# RFID_transmitter_V2.net
KiCad netlist of a schematic drawn in Altium Designer
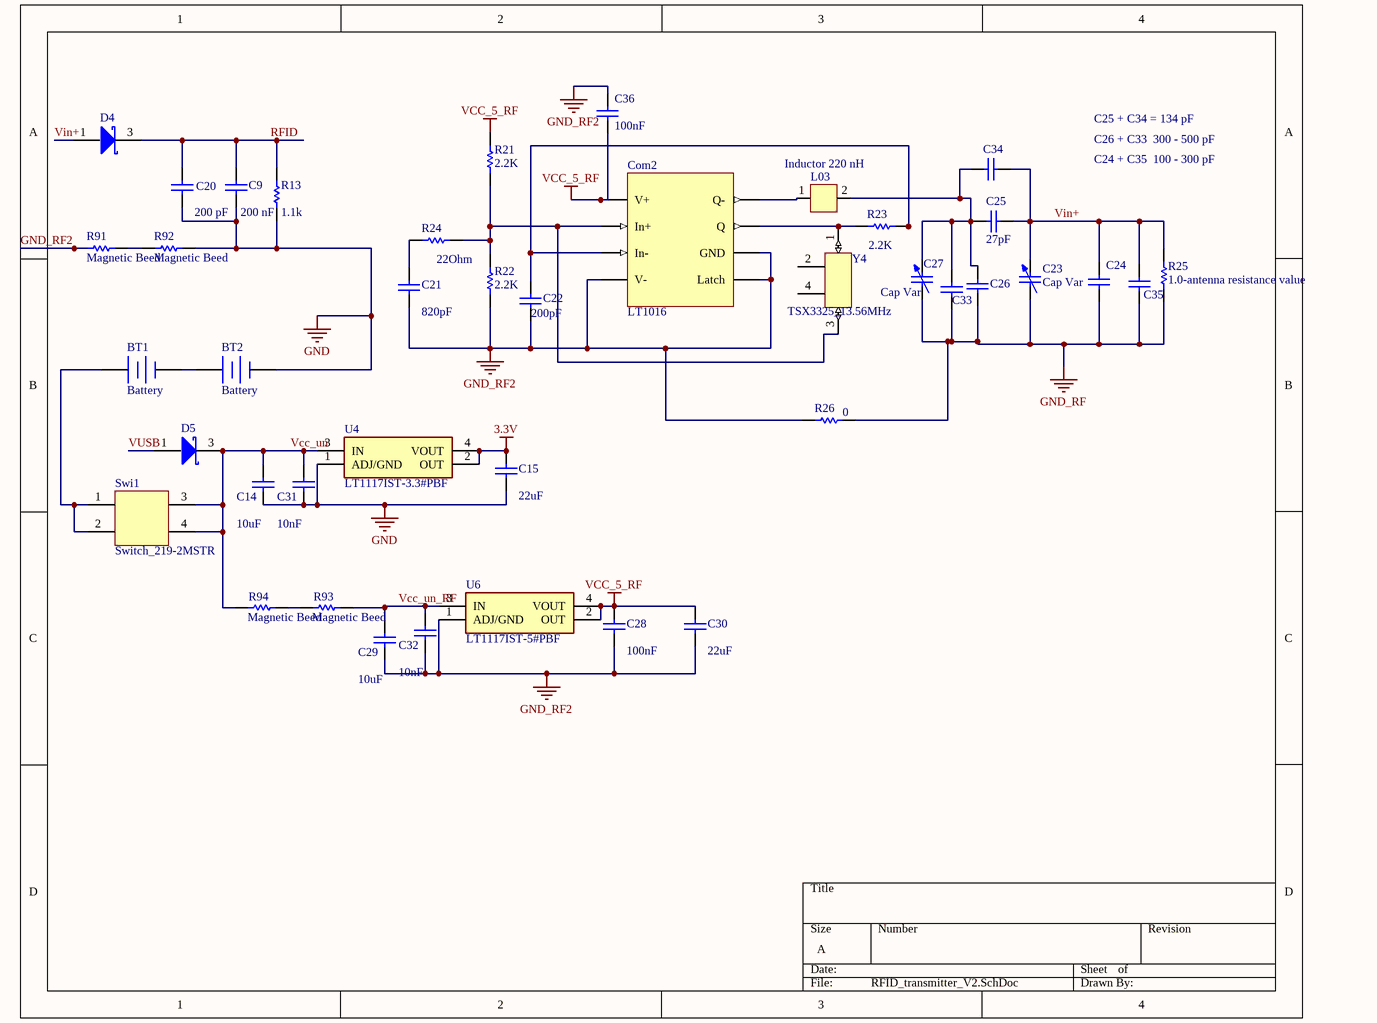
[diagram p0: RFID_transmitter_V2.SchDoc]

(export (version "E")
  (design (tool "Eeschema 10.0.6"))
  (components
    (comp (ref "BT1")
      (value "Battery")
      (footprint "Battery")
      (description "Multicell Battery")
      (fields (field (name "PUBLISHER") "Altium Limited"))
      (libsource (lib "Miscellaneous Devices") (part "Battery"))
    )
    (comp (ref "BT2")
      (value "Battery")
      (footprint "Battery")
      (description "Multicell Battery")
      (fields (field (name "PUBLISHER") "Altium Limited"))
      (libsource (lib "Miscellaneous Devices") (part "Battery"))
    )
    (comp (ref "C9")
      (value "200 nF")
      (footprint "0603")
      (description "Capacitor")
      (fields (field (name "Comment") "Cap 10n") (field (name "PUBLISHER") "Altium Limited"))
      (libsource (lib "Miscellaneous Devices") (part "Cap"))
    )
    (comp (ref "C14")
      (value "10uF")
      (footprint "0603")
      (description "Capacitor")
      (fields (field (name "Comment") "Cap 10u") (field (name "PUBLISHER") "Altium Limited"))
      (libsource (lib "Miscellaneous Devices") (part "Cap"))
    )
    (comp (ref "C15")
      (value "22uF")
      (footprint "0603")
      (description "Capacitor")
      (fields (field (name "Comment") "Cap 22u") (field (name "PUBLISHER") "Altium Limited"))
      (libsource (lib "Miscellaneous Devices") (part "Cap"))
    )
    (comp (ref "C20")
      (value "200 pF")
      (footprint "0603")
      (description "Capacitor")
      (fields (field (name "Comment") "Cap 4.7n") (field (name "PUBLISHER") "Altium Limited"))
      (libsource (lib "Miscellaneous Devices") (part "Cap"))
    )
    (comp (ref "C21")
      (value "820pF")
      (footprint "0603")
      (description "Capacitor")
      (fields (field (name "Comment") "Cap 820p") (field (name "PUBLISHER") "Altium Limited"))
      (libsource (lib "Miscellaneous Devices") (part "Cap"))
    )
    (comp (ref "C22")
      (value "200pF")
      (footprint "0603")
      (description "Capacitor")
      (fields (field (name "Comment") "Cap 200p") (field (name "PUBLISHER") "Altium Limited"))
      (libsource (lib "Miscellaneous Devices") (part "Cap"))
    )
    (comp (ref "C23")
      (value "Cap Var")
      (footprint "Variable_Capacitor_JZ400HV1")
      (description "Variable or Adjustable Capacitor")
      (fields (field (name "PUBLISHER") "Altium Limited"))
      (libsource (lib "Miscellaneous Devices") (part "Cap Var"))
    )
    (comp (ref "C24")
      (value "Cap")
      (footprint "0603")
      (description "Capacitor_for resonance")
      (fields (field (name "PUBLISHER") "Altium Limited"))
      (libsource (lib "Miscellaneous Devices") (part "Cap"))
    )
    (comp (ref "C25")
      (value "27pF")
      (footprint "0603")
      (description "Capacitor_for resonance")
      (fields (field (name "Comment") "Cap") (field (name "PUBLISHER") "Altium Limited"))
      (libsource (lib "Miscellaneous Devices") (part "Cap"))
    )
    (comp (ref "C26")
      (value "random value needs carefully address")
      (footprint "0603")
      (description "Capacitor_for resonance")
      (fields (field (name "PUBLISHER") "Altium Limited"))
      (libsource (lib "Miscellaneous Devices") (part "Cap"))
    )
    (comp (ref "C27")
      (value "Cap Var")
      (footprint "Variable_Capacitor_JZ400HV1")
      (description "Variable or Adjustable Capacitor")
      (fields (field (name "PUBLISHER") "Altium Limited"))
      (libsource (lib "Miscellaneous Devices") (part "Cap Var"))
    )
    (comp (ref "C28")
      (value "100nF")
      (footprint "0603")
      (description "Capacitor")
      (fields (field (name "Comment") "Cap 100n") (field (name "PUBLISHER") "Altium Limited"))
      (libsource (lib "Miscellaneous Devices") (part "Cap"))
    )
    (comp (ref "C29")
      (value "10uF")
      (footprint "0603")
      (description "Capacitor")
      (fields (field (name "Comment") "Cap 10u") (field (name "PUBLISHER") "Altium Limited"))
      (libsource (lib "Miscellaneous Devices") (part "Cap"))
    )
    (comp (ref "C30")
      (value "22uF")
      (footprint "0603")
      (description "Capacitor")
      (fields (field (name "Comment") "Cap 22u") (field (name "PUBLISHER") "Altium Limited"))
      (libsource (lib "Miscellaneous Devices") (part "Cap"))
    )
    (comp (ref "C31")
      (value "10nF")
      (footprint "0603")
      (description "Capacitor")
      (fields (field (name "Comment") "Cap 10n") (field (name "PUBLISHER") "Altium Limited"))
      (libsource (lib "Miscellaneous Devices") (part "Cap"))
    )
    (comp (ref "C32")
      (value "10nF")
      (footprint "0603")
      (description "Capacitor")
      (fields (field (name "Comment") "Cap 10n") (field (name "PUBLISHER") "Altium Limited"))
      (libsource (lib "Miscellaneous Devices") (part "Cap"))
    )
    (comp (ref "C33")
      (value "random value needs carefully address")
      (footprint "0603")
      (description "Capacitor_for resonance")
      (fields (field (name "PUBLISHER") "Altium Limited"))
      (libsource (lib "Miscellaneous Devices") (part "Cap"))
    )
    (comp (ref "C34")
      (value "Cap")
      (footprint "0603")
      (description "Capacitor_for resonance")
      (fields (field (name "PUBLISHER") "Altium Limited"))
      (libsource (lib "Miscellaneous Devices") (part "Cap"))
    )
    (comp (ref "C35")
      (value "Cap")
      (footprint "0603")
      (description "Capacitor_for resonance")
      (fields (field (name "PUBLISHER") "Altium Limited"))
      (libsource (lib "Miscellaneous Devices") (part "Cap"))
    )
    (comp (ref "C36")
      (value "100nF")
      (footprint "1608[0603]")
      (description "Capacitor (Semiconductor SIM Model)")
      (fields
        (field (name "VOLTAGE") "10V")
        (field (name "Comment") "GRM188R61A226ME15D")
        (field (name "PUBLISHER") "Altium Limited")
      )
      (libsource (lib "Miscellaneous Devices") (part "Cap Semi"))
    )
    (comp (ref "Com2") (value "LT1016") (footprint "LT1016_SOIC") (libsource (lib "LT1016") (part "LT1016")))
    (comp (ref "D4")
      (value "SMMBD301LT3G")
      (footprint "SamacSys:SOT96P237X111-3N")
      (description "Schottky Barrier Diodes")
      (libsource (lib "SamacSys") (part "SMMBD301LT3G"))
    )
    (comp (ref "D5")
      (value "SMMBD301LT3G")
      (footprint "SamacSys:SOT96P237X111-3N")
      (description "Schottky Barrier Diodes")
      (libsource (lib "SamacSys") (part "SMMBD301LT3G"))
    )
    (comp (ref "L03")
      (value "Inductor 220 nH")
      (footprint "Ferrite_bead_0805inch_2012mm")
      (description "220nH")
      (libsource (lib "ferrite_bead") (part "Component_1"))
    )
    (comp (ref "R13")
      (value "1.1k")
      (footprint "0603")
      (description "Resistor")
      (fields (field (name "Comment") "Res1") (field (name "PUBLISHER") "Altium Limited"))
      (libsource (lib "Miscellaneous Devices") (part "Res1"))
    )
    (comp (ref "R21")
      (value "2.2K")
      (footprint "0603")
      (description "Resistor")
      (fields (field (name "Comment") "Res1 2.2k") (field (name "PUBLISHER") "Altium Limited"))
      (libsource (lib "Miscellaneous Devices") (part "Res1"))
    )
    (comp (ref "R22")
      (value "2.2K")
      (footprint "0603")
      (description "Resistor")
      (fields (field (name "Comment") "Res1 2.2k") (field (name "PUBLISHER") "Altium Limited"))
      (libsource (lib "Miscellaneous Devices") (part "Res1"))
    )
    (comp (ref "R23")
      (value "2.2K")
      (footprint "0603")
      (description "Resistor")
      (fields (field (name "Comment") "Res1 2.2k") (field (name "PUBLISHER") "Altium Limited"))
      (libsource (lib "Miscellaneous Devices") (part "Res1"))
    )
    (comp (ref "R24")
      (value "22Ohm")
      (footprint "0603")
      (description "Resistor")
      (fields (field (name "Comment") "Res1 22") (field (name "PUBLISHER") "Altium Limited"))
      (libsource (lib "Miscellaneous Devices") (part "Res1"))
    )
    (comp (ref "R25")
      (value "1.0-antenna resistance value")
      (footprint "0603")
      (description "Resistor")
      (fields (field (name "PUBLISHER") "Altium Limited"))
      (libsource (lib "Miscellaneous Devices") (part "Res1"))
    )
    (comp (ref "R26")
      (value "0")
      (footprint "0603")
      (description "Wurth Magnetic Bead")
      (fields (field (name "Comment") "Magnetic Beed") (field (name "PUBLISHER") "Altium Limited"))
      (libsource (lib "Miscellaneous Devices") (part "Res1"))
    )
    (comp (ref "R91")
      (value "Magnetic Beed")
      (footprint "0603")
      (description "Wurth Magnetic Bead")
      (fields (field (name "PUBLISHER") "Altium Limited"))
      (libsource (lib "Miscellaneous Devices") (part "Res1"))
    )
    (comp (ref "R92")
      (value "Magnetic Beed")
      (footprint "0603")
      (description "Wurth Magnetic Bead")
      (fields (field (name "PUBLISHER") "Altium Limited"))
      (libsource (lib "Miscellaneous Devices") (part "Res1"))
    )
    (comp (ref "R93")
      (value "Magnetic Beed")
      (footprint "0603")
      (description "Resistor")
      (fields (field (name "PUBLISHER") "Altium Limited"))
      (libsource (lib "Miscellaneous Devices") (part "Res1"))
    )
    (comp (ref "R94")
      (value "Magnetic Beed")
      (footprint "0603")
      (description "Resistor")
      (fields (field (name "PUBLISHER") "Altium Limited"))
      (libsource (lib "Miscellaneous Devices") (part "Res1"))
    )
    (comp (ref "Swi1")
      (value "Switch_219-2MSTR")
      (footprint "Switch_219-2MSTR")
      (libsource (lib "Switch_219-2MSTR") (part "Switch_219-2MSTR"))
    )
    (comp (ref "U4")
      (value "LT1117IST-3.3#PBF")
      (footprint "SamacSys:SOT230P700X180-4N")
      (description "Integrated Circuit")
      (fields (field (name "MOUSER PART NUMBER") "584-LT1117IST-3.3PBF"))
      (libsource (lib "SamacSys") (part "LT1117IST-3.3#PBF"))
    )
    (comp (ref "U6")
      (value "LT1117IST-5#PBF")
      (footprint "SamacSys:SOT230P700X180-4N")
      (libsource (lib "SamacSys") (part "LT1117IST-5#PBF"))
    )
    (comp (ref "Y4")
      (value "TSX3325_13.56MHz")
      (footprint "HC_49Crystal")
      (libsource (lib "TSX3325") (part "TSX3325"))
    )
  )
  (nets
    (net (code "1") (name "/RFID") (class "Default")
      (node (ref "C20") (pin "2") (pinfunction "2_2") (pintype "passive"))
      (node (ref "C9") (pin "2") (pinfunction "2_2") (pintype "passive"))
      (node (ref "D4") (pin "3") (pinfunction "CATHODE_3") (pintype "passive"))
      (node (ref "R13") (pin "2") (pinfunction "2_2") (pintype "passive"))
    )
    (net (code "2") (name "/VUSB") (class "Default")
      (node (ref "D5") (pin "1") (pinfunction "ANODE_1") (pintype "passive"))
    )
    (net (code "3") (name "/Vcc_un") (class "Default")
      (node (ref "C14") (pin "2") (pinfunction "2_2") (pintype "passive"))
      (node (ref "C31") (pin "2") (pinfunction "2_2") (pintype "passive"))
      (node (ref "D5") (pin "3") (pinfunction "CATHODE_3") (pintype "passive"))
      (node (ref "R94") (pin "1") (pinfunction "1_1") (pintype "passive"))
      (node (ref "Swi1") (pin "3") (pinfunction "Out1_3") (pintype "power_in"))
      (node (ref "Swi1") (pin "4") (pinfunction "Out2_4") (pintype "power_in"))
      (node (ref "U4") (pin "3") (pinfunction "IN_3") (pintype "passive"))
    )
    (net (code "4") (name "/Vcc_un_RF") (class "Default")
      (node (ref "C29") (pin "2") (pinfunction "2_2") (pintype "passive"))
      (node (ref "C32") (pin "2") (pinfunction "2_2") (pintype "passive"))
      (node (ref "R93") (pin "2") (pinfunction "2_2") (pintype "passive"))
      (node (ref "U6") (pin "3") (pinfunction "IN_3") (pintype "passive"))
    )
    (net (code "5") (name "/Vin+") (class "Default")
      (node (ref "C23") (pin "2") (pinfunction "2_2") (pintype "passive"))
      (node (ref "C24") (pin "2") (pinfunction "2_2") (pintype "passive"))
      (node (ref "C25") (pin "1") (pinfunction "1_1") (pintype "passive"))
      (node (ref "C34") (pin "1") (pinfunction "1_1") (pintype "passive"))
      (node (ref "C35") (pin "2") (pinfunction "2_2") (pintype "passive"))
      (node (ref "D4") (pin "1") (pinfunction "ANODE_1") (pintype "passive"))
      (node (ref "R25") (pin "2") (pinfunction "2_2") (pintype "passive"))
    )
    (net (code "6") (name "3.3V") (class "Default")
      (node (ref "C15") (pin "2") (pinfunction "2_2") (pintype "passive"))
      (node (ref "U4") (pin "2") (pinfunction "OUT_2") (pintype "passive"))
      (node (ref "U4") (pin "4") (pinfunction "VOUT_4") (pintype "passive"))
    )
    (net (code "7") (name "GND") (class "Default")
      (node (ref "BT2") (pin "2") (pinfunction "-_2") (pintype "passive"))
      (node (ref "C14") (pin "1") (pinfunction "1_1") (pintype "passive"))
      (node (ref "C15") (pin "1") (pinfunction "1_1") (pintype "passive"))
      (node (ref "C20") (pin "1") (pinfunction "1_1") (pintype "passive"))
      (node (ref "C31") (pin "1") (pinfunction "1_1") (pintype "passive"))
      (node (ref "C9") (pin "1") (pinfunction "1_1") (pintype "passive"))
      (node (ref "R13") (pin "1") (pinfunction "1_1") (pintype "passive"))
      (node (ref "R92") (pin "2") (pinfunction "2_2") (pintype "passive"))
      (node (ref "U4") (pin "1") (pinfunction "ADJ/GND_1") (pintype "passive"))
    )
    (net (code "8") (name "GND_RF") (class "Default")
      (node (ref "C23") (pin "1") (pinfunction "1_1") (pintype "passive"))
      (node (ref "C24") (pin "1") (pinfunction "1_1") (pintype "passive"))
      (node (ref "C26") (pin "2") (pinfunction "2_2") (pintype "passive"))
      (node (ref "C27") (pin "1") (pinfunction "1_1") (pintype "passive"))
      (node (ref "C33") (pin "2") (pinfunction "2_2") (pintype "passive"))
      (node (ref "C35") (pin "1") (pinfunction "1_1") (pintype "passive"))
      (node (ref "R25") (pin "1") (pinfunction "1_1") (pintype "passive"))
      (node (ref "R26") (pin "2") (pinfunction "2_2") (pintype "passive"))
    )
    (net (code "9") (name "GND_RF2") (class "Default")
      (node (ref "C21") (pin "1") (pinfunction "1_1") (pintype "passive"))
      (node (ref "C22") (pin "1") (pinfunction "1_1") (pintype "passive"))
      (node (ref "C28") (pin "1") (pinfunction "1_1") (pintype "passive"))
      (node (ref "C29") (pin "1") (pinfunction "1_1") (pintype "passive"))
      (node (ref "C30") (pin "1") (pinfunction "1_1") (pintype "passive"))
      (node (ref "C32") (pin "1") (pinfunction "1_1") (pintype "passive"))
      (node (ref "C36") (pin "2") (pinfunction "2_2") (pintype "passive"))
      (node (ref "Com2") (pin "4") (pinfunction "V-_4") (pintype "power_in"))
      (node (ref "Com2") (pin "5") (pinfunction "Latch_5") (pintype "passive"))
      (node (ref "Com2") (pin "6") (pinfunction "GND_6") (pintype "power_in"))
      (node (ref "R22") (pin "1") (pinfunction "1_1") (pintype "passive"))
      (node (ref "R26") (pin "1") (pinfunction "1_1") (pintype "passive"))
      (node (ref "R91") (pin "1") (pinfunction "1_1") (pintype "passive"))
      (node (ref "U6") (pin "1") (pinfunction "ADJ/GND_1") (pintype "passive"))
    )
    (net (code "10") (name "Net-(BT1-+)") (class "Default")
      (node (ref "BT1") (pin "1") (pinfunction "+_1") (pintype "passive"))
      (node (ref "Swi1") (pin "1") (pinfunction "In1_1") (pintype "power_in"))
      (node (ref "Swi1") (pin "2") (pinfunction "In2_2") (pintype "power_in"))
    )
    (net (code "11") (name "Net-(BT1--)") (class "Default")
      (node (ref "BT1") (pin "2") (pinfunction "-_2") (pintype "passive"))
      (node (ref "BT2") (pin "1") (pinfunction "+_1") (pintype "passive"))
    )
    (net (code "12") (name "Net-(C21-Pad2)") (class "Default")
      (node (ref "C21") (pin "2") (pinfunction "2_2") (pintype "passive"))
      (node (ref "R24") (pin "1") (pinfunction "1_1") (pintype "passive"))
    )
    (net (code "13") (name "Net-(C25-Pad2)") (class "Default")
      (node (ref "C25") (pin "2") (pinfunction "2_2") (pintype "passive"))
      (node (ref "C26") (pin "1") (pinfunction "1_1") (pintype "passive"))
      (node (ref "C27") (pin "2") (pinfunction "2_2") (pintype "passive"))
      (node (ref "C33") (pin "1") (pinfunction "1_1") (pintype "passive"))
      (node (ref "C34") (pin "2") (pinfunction "2_2") (pintype "passive"))
      (node (ref "L03") (pin "2") (pinfunction "2_2") (pintype "passive"))
    )
    (net (code "14") (name "Net-(Com2-In+)") (class "Default")
      (node (ref "Com2") (pin "2") (pinfunction "In+_2") (pintype "input"))
      (node (ref "R21") (pin "1") (pinfunction "1_1") (pintype "passive"))
      (node (ref "R22") (pin "2") (pinfunction "2_2") (pintype "passive"))
      (node (ref "R24") (pin "2") (pinfunction "2_2") (pintype "passive"))
      (node (ref "Y4") (pin "3") (pinfunction "Out_3") (pintype "bidirectional"))
    )
    (net (code "15") (name "Net-(Com2-In-)") (class "Default")
      (node (ref "C22") (pin "2") (pinfunction "2_2") (pintype "passive"))
      (node (ref "Com2") (pin "3") (pinfunction "In-_3") (pintype "input"))
      (node (ref "R23") (pin "2") (pinfunction "2_2") (pintype "passive"))
    )
    (net (code "16") (name "Net-(Com2-Q)") (class "Default")
      (node (ref "Com2") (pin "7") (pinfunction "Q_7") (pintype "output"))
      (node (ref "R23") (pin "1") (pinfunction "1_1") (pintype "passive"))
      (node (ref "Y4") (pin "1") (pinfunction "In_1") (pintype "bidirectional"))
    )
    (net (code "17") (name "Net-(Com2-Q-)") (class "Default")
      (node (ref "Com2") (pin "8") (pinfunction "Q-_8") (pintype "output"))
      (node (ref "L03") (pin "1") (pinfunction "1_1") (pintype "passive"))
    )
    (net (code "18") (name "Net-(R91-Pad2)") (class "Default")
      (node (ref "R91") (pin "2") (pinfunction "2_2") (pintype "passive"))
      (node (ref "R92") (pin "1") (pinfunction "1_1") (pintype "passive"))
    )
    (net (code "19") (name "Net-(R93-Pad1)") (class "Default")
      (node (ref "R93") (pin "1") (pinfunction "1_1") (pintype "passive"))
      (node (ref "R94") (pin "2") (pinfunction "2_2") (pintype "passive"))
    )
    (net (code "20") (name "VCC_5_RF") (class "Default")
      (node (ref "C28") (pin "2") (pinfunction "2_2") (pintype "passive"))
      (node (ref "C30") (pin "2") (pinfunction "2_2") (pintype "passive"))
      (node (ref "C36") (pin "1") (pinfunction "1_1") (pintype "passive"))
      (node (ref "Com2") (pin "1") (pinfunction "V+_1") (pintype "passive"))
      (node (ref "R21") (pin "2") (pinfunction "2_2") (pintype "passive"))
      (node (ref "U6") (pin "2") (pinfunction "OUT_2") (pintype "passive"))
      (node (ref "U6") (pin "4") (pinfunction "VOUT_4") (pintype "passive"))
    )
    (net (code "21") (name "unconnected-(Y4-GND-Pad2)") (class "Default")
      (node (ref "Y4") (pin "2") (pinfunction "GND_2") (pintype "power_in"))
    )
    (net (code "22") (name "unconnected-(Y4-GND-Pad4)") (class "Default")
      (node (ref "Y4") (pin "4") (pinfunction "GND_4") (pintype "power_in"))
    )
  )
)
